# Schematic.net
KiCad netlist of a schematic drawn in EAGLE
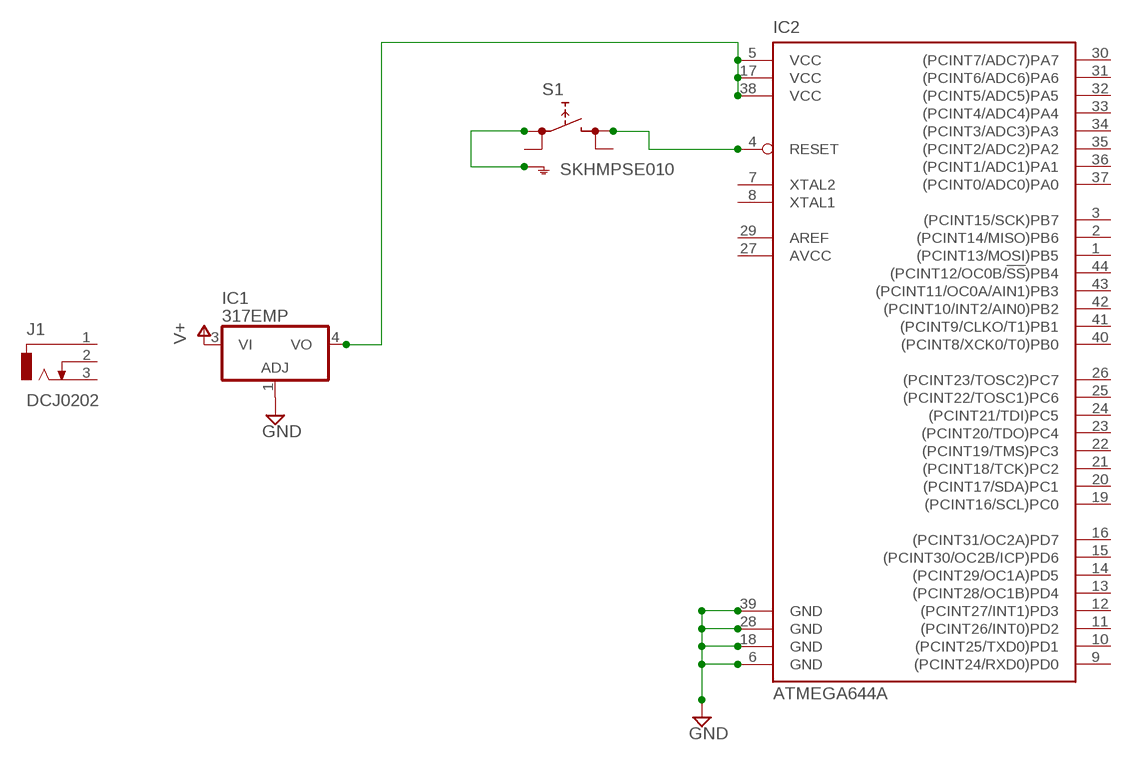
[diagram p0: schematic, sheet 1]

(export (version "E")
  (design (tool "Eeschema 10.0.6"))
  (components
    (comp (ref "IC1")
      (value "317EMP")
      (footprint "eagle-import:SOT223")
      (libsource (lib "eagle-import") (part "317EMP"))
    )
    (comp (ref "IC2")
      (value "ATMEGA644A")
      (footprint "eagle-import:TQFP44")
      (fields (field (name "MPN") "ATMEGA644PV-10AU"))
      (libsource (lib "eagle-import") (part "ATMEGA644A"))
    )
    (comp (ref "J1")
      (value "DCJ0202")
      (footprint "eagle-import:DCJ0202")
      (libsource (lib "eagle-import") (part "DCJ0202"))
    )
    (comp (ref "S1")
      (value "SKHMPSE010")
      (footprint "eagle-import:SKHMPXE010")
      (libsource (lib "eagle-import") (part "SKHMPE010S"))
    )
  )
  (nets
    (net (code "1") (name "/AVCC") (class "Default")
      (node (ref "IC2") (pin "27") (pinfunction "AVCC_27") (pintype "power_in"))
    )
    (net (code "2") (name "GND") (class "Default")
      (node (ref "IC1") (pin "1") (pinfunction "ADJ_1") (pintype "input"))
      (node (ref "IC2") (pin "18") (pinfunction "GND_18") (pintype "power_in"))
      (node (ref "IC2") (pin "28") (pinfunction "GND_28") (pintype "power_in"))
      (node (ref "IC2") (pin "39") (pinfunction "GND_39") (pintype "power_in"))
      (node (ref "IC2") (pin "6") (pinfunction "GND_6") (pintype "power_in"))
    )
    (net (code "3") (name "Net-(IC1-VO)") (class "Default")
      (node (ref "IC1") (pin "4") (pinfunction "VO_4") (pintype "passive"))
      (node (ref "IC2") (pin "17") (pinfunction "VCC_17") (pintype "power_in"))
      (node (ref "IC2") (pin "38") (pinfunction "VCC_38") (pintype "power_in"))
      (node (ref "IC2") (pin "5") (pinfunction "VCC_5") (pintype "power_in"))
    )
    (net (code "4") (name "Net-(IC2-RESET)") (class "Default")
      (node (ref "IC2") (pin "4") (pinfunction "RESET_4") (pintype "input"))
      (node (ref "S1") (pin "3") (pinfunction "2.1_3") (pintype "passive"))
    )
    (net (code "5") (name "Net-(S1-1.1)") (class "Default")
      (node (ref "S1") (pin "1") (pinfunction "1.1_1") (pintype "passive"))
      (node (ref "S1") (pin "5") (pinfunction "SH_5") (pintype "passive"))
    )
    (net (code "6") (name "V+") (class "Default")
      (node (ref "IC1") (pin "3") (pinfunction "VI_3") (pintype "input"))
    )
    (net (code "7") (name "unconnected-(IC2-(PCINT0{slash}ADC0)PA0-Pad37)") (class "Default")
      (node (ref "IC2") (pin "37") (pinfunction "(PCINT0/ADC0)PA0_37") (pintype "bidirectional"))
    )
    (net (code "8") (name "unconnected-(IC2-(PCINT1{slash}ADC1)PA1-Pad36)") (class "Default")
      (node (ref "IC2") (pin "36") (pinfunction "(PCINT1/ADC1)PA1_36") (pintype "bidirectional"))
    )
    (net (code "9") (name "unconnected-(IC2-(PCINT2{slash}ADC2)PA2-Pad35)") (class "Default")
      (node (ref "IC2") (pin "35") (pinfunction "(PCINT2/ADC2)PA2_35") (pintype "bidirectional"))
    )
    (net (code "10") (name "unconnected-(IC2-(PCINT3{slash}ADC3)PA3-Pad34)") (class "Default")
      (node (ref "IC2") (pin "34") (pinfunction "(PCINT3/ADC3)PA3_34") (pintype "bidirectional"))
    )
    (net (code "11") (name "unconnected-(IC2-(PCINT4{slash}ADC4)PA4-Pad33)") (class "Default")
      (node (ref "IC2") (pin "33") (pinfunction "(PCINT4/ADC4)PA4_33") (pintype "bidirectional"))
    )
    (net (code "12") (name "unconnected-(IC2-(PCINT5{slash}ADC5)PA5-Pad32)") (class "Default")
      (node (ref "IC2") (pin "32") (pinfunction "(PCINT5/ADC5)PA5_32") (pintype "bidirectional"))
    )
    (net (code "13") (name "unconnected-(IC2-(PCINT6{slash}ADC6)PA6-Pad31)") (class "Default")
      (node (ref "IC2") (pin "31") (pinfunction "(PCINT6/ADC6)PA6_31") (pintype "bidirectional"))
    )
    (net (code "14") (name "unconnected-(IC2-(PCINT7{slash}ADC7)PA7-Pad30)") (class "Default")
      (node (ref "IC2") (pin "30") (pinfunction "(PCINT7/ADC7)PA7_30") (pintype "bidirectional"))
    )
    (net (code "15") (name "unconnected-(IC2-(PCINT8{slash}XCK0{slash}T0)PB0-Pad40)") (class "Default")
      (node (ref "IC2") (pin "40") (pinfunction "(PCINT8/XCK0/T0)PB0_40") (pintype "bidirectional"))
    )
    (net (code "16") (name "unconnected-(IC2-(PCINT9{slash}CLKO{slash}T1)PB1-Pad41)") (class "Default")
      (node (ref "IC2") (pin "41") (pinfunction "(PCINT9/CLKO/T1)PB1_41") (pintype "bidirectional"))
    )
    (net (code "17") (name "unconnected-(IC2-(PCINT10{slash}INT2{slash}AIN0)PB2-Pad42)") (class "Default")
      (node (ref "IC2") (pin "42") (pinfunction "(PCINT10/INT2/AIN0)PB2_42") (pintype "bidirectional"))
    )
    (net (code "18") (name "unconnected-(IC2-(PCINT11{slash}OC0A{slash}AIN1)PB3-Pad43)") (class "Default")
      (node (ref "IC2") (pin "43") (pinfunction "(PCINT11/OC0A/AIN1)PB3_43") (pintype "bidirectional"))
    )
    (net (code "19") (name "unconnected-(IC2-(PCINT12{slash}OC0B{slash}~{SS})PB4-Pad44)") (class "Default")
      (node (ref "IC2") (pin "44") (pinfunction "(PCINT12/OC0B/~{SS})PB4_44") (pintype "bidirectional"))
    )
    (net (code "20") (name "unconnected-(IC2-(PCINT13{slash}MOSI)PB5-Pad1)") (class "Default")
      (node (ref "IC2") (pin "1") (pinfunction "(PCINT13/MOSI)PB5_1") (pintype "bidirectional"))
    )
    (net (code "21") (name "unconnected-(IC2-(PCINT14{slash}MISO)PB6-Pad2)") (class "Default")
      (node (ref "IC2") (pin "2") (pinfunction "(PCINT14/MISO)PB6_2") (pintype "bidirectional"))
    )
    (net (code "22") (name "unconnected-(IC2-(PCINT15{slash}SCK)PB7-Pad3)") (class "Default")
      (node (ref "IC2") (pin "3") (pinfunction "(PCINT15/SCK)PB7_3") (pintype "bidirectional"))
    )
    (net (code "23") (name "unconnected-(IC2-(PCINT16{slash}SCL)PC0-Pad19)") (class "Default")
      (node (ref "IC2") (pin "19") (pinfunction "(PCINT16/SCL)PC0_19") (pintype "output"))
    )
    (net (code "24") (name "unconnected-(IC2-(PCINT17{slash}SDA)PC1-Pad20)") (class "Default")
      (node (ref "IC2") (pin "20") (pinfunction "(PCINT17/SDA)PC1_20") (pintype "output"))
    )
    (net (code "25") (name "unconnected-(IC2-(PCINT18{slash}TCK)PC2-Pad21)") (class "Default")
      (node (ref "IC2") (pin "21") (pinfunction "(PCINT18/TCK)PC2_21") (pintype "output"))
    )
    (net (code "26") (name "unconnected-(IC2-(PCINT19{slash}TMS)PC3-Pad22)") (class "Default")
      (node (ref "IC2") (pin "22") (pinfunction "(PCINT19/TMS)PC3_22") (pintype "output"))
    )
    (net (code "27") (name "unconnected-(IC2-(PCINT20{slash}TDO)PC4-Pad23)") (class "Default")
      (node (ref "IC2") (pin "23") (pinfunction "(PCINT20/TDO)PC4_23") (pintype "output"))
    )
    (net (code "28") (name "unconnected-(IC2-(PCINT21{slash}TDI)PC5-Pad24)") (class "Default")
      (node (ref "IC2") (pin "24") (pinfunction "(PCINT21/TDI)PC5_24") (pintype "output"))
    )
    (net (code "29") (name "unconnected-(IC2-(PCINT22{slash}TOSC1)PC6-Pad25)") (class "Default")
      (node (ref "IC2") (pin "25") (pinfunction "(PCINT22/TOSC1)PC6_25") (pintype "output"))
    )
    (net (code "30") (name "unconnected-(IC2-(PCINT23{slash}TOSC2)PC7-Pad26)") (class "Default")
      (node (ref "IC2") (pin "26") (pinfunction "(PCINT23/TOSC2)PC7_26") (pintype "output"))
    )
    (net (code "31") (name "unconnected-(IC2-(PCINT24{slash}RXD0)PD0-Pad9)") (class "Default")
      (node (ref "IC2") (pin "9") (pinfunction "(PCINT24/RXD0)PD0_9") (pintype "bidirectional"))
    )
    (net (code "32") (name "unconnected-(IC2-(PCINT25{slash}TXD0)PD1-Pad10)") (class "Default")
      (node (ref "IC2") (pin "10") (pinfunction "(PCINT25/TXD0)PD1_10") (pintype "bidirectional"))
    )
    (net (code "33") (name "unconnected-(IC2-(PCINT26{slash}INT0)PD2-Pad11)") (class "Default")
      (node (ref "IC2") (pin "11") (pinfunction "(PCINT26/INT0)PD2_11") (pintype "bidirectional"))
    )
    (net (code "34") (name "unconnected-(IC2-(PCINT27{slash}INT1)PD3-Pad12)") (class "Default")
      (node (ref "IC2") (pin "12") (pinfunction "(PCINT27/INT1)PD3_12") (pintype "bidirectional"))
    )
    (net (code "35") (name "unconnected-(IC2-(PCINT28{slash}OC1B)PD4-Pad13)") (class "Default")
      (node (ref "IC2") (pin "13") (pinfunction "(PCINT28/OC1B)PD4_13") (pintype "bidirectional"))
    )
    (net (code "36") (name "unconnected-(IC2-(PCINT29{slash}OC1A)PD5-Pad14)") (class "Default")
      (node (ref "IC2") (pin "14") (pinfunction "(PCINT29/OC1A)PD5_14") (pintype "bidirectional"))
    )
    (net (code "37") (name "unconnected-(IC2-(PCINT30{slash}OC2B{slash}ICP)PD6-Pad15)") (class "Default")
      (node (ref "IC2") (pin "15") (pinfunction "(PCINT30/OC2B/ICP)PD6_15") (pintype "bidirectional"))
    )
    (net (code "38") (name "unconnected-(IC2-(PCINT31{slash}OC2A)PD7-Pad16)") (class "Default")
      (node (ref "IC2") (pin "16") (pinfunction "(PCINT31/OC2A)PD7_16") (pintype "bidirectional"))
    )
    (net (code "39") (name "unconnected-(IC2-AREF-Pad29)") (class "Default")
      (node (ref "IC2") (pin "29") (pinfunction "AREF_29") (pintype "passive"))
    )
    (net (code "40") (name "unconnected-(IC2-XTAL1-Pad8)") (class "Default")
      (node (ref "IC2") (pin "8") (pinfunction "XTAL1_8") (pintype "bidirectional"))
    )
    (net (code "41") (name "unconnected-(IC2-XTAL2-Pad7)") (class "Default")
      (node (ref "IC2") (pin "7") (pinfunction "XTAL2_7") (pintype "bidirectional"))
    )
    (net (code "42") (name "unconnected-(J1-Pad1)") (class "Default")
      (node (ref "J1") (pin "1") (pinfunction "1_1") (pintype "passive"))
    )
    (net (code "43") (name "unconnected-(J1-Pad2)") (class "Default")
      (node (ref "J1") (pin "2") (pinfunction "2_2") (pintype "passive"))
    )
    (net (code "44") (name "unconnected-(J1-Pad3)") (class "Default")
      (node (ref "J1") (pin "3") (pinfunction "3_3") (pintype "passive"))
    )
    (net (code "45") (name "unconnected-(S1-1.2-Pad2)") (class "Default")
      (node (ref "S1") (pin "2") (pinfunction "1.2_2") (pintype "passive"))
    )
    (net (code "46") (name "unconnected-(S1-2.2-Pad4)") (class "Default")
      (node (ref "S1") (pin "4") (pinfunction "2.2_4") (pintype "passive"))
    )
  )
)
